# Sche_Main.net
KiCad netlist of a schematic drawn in Altium Designer
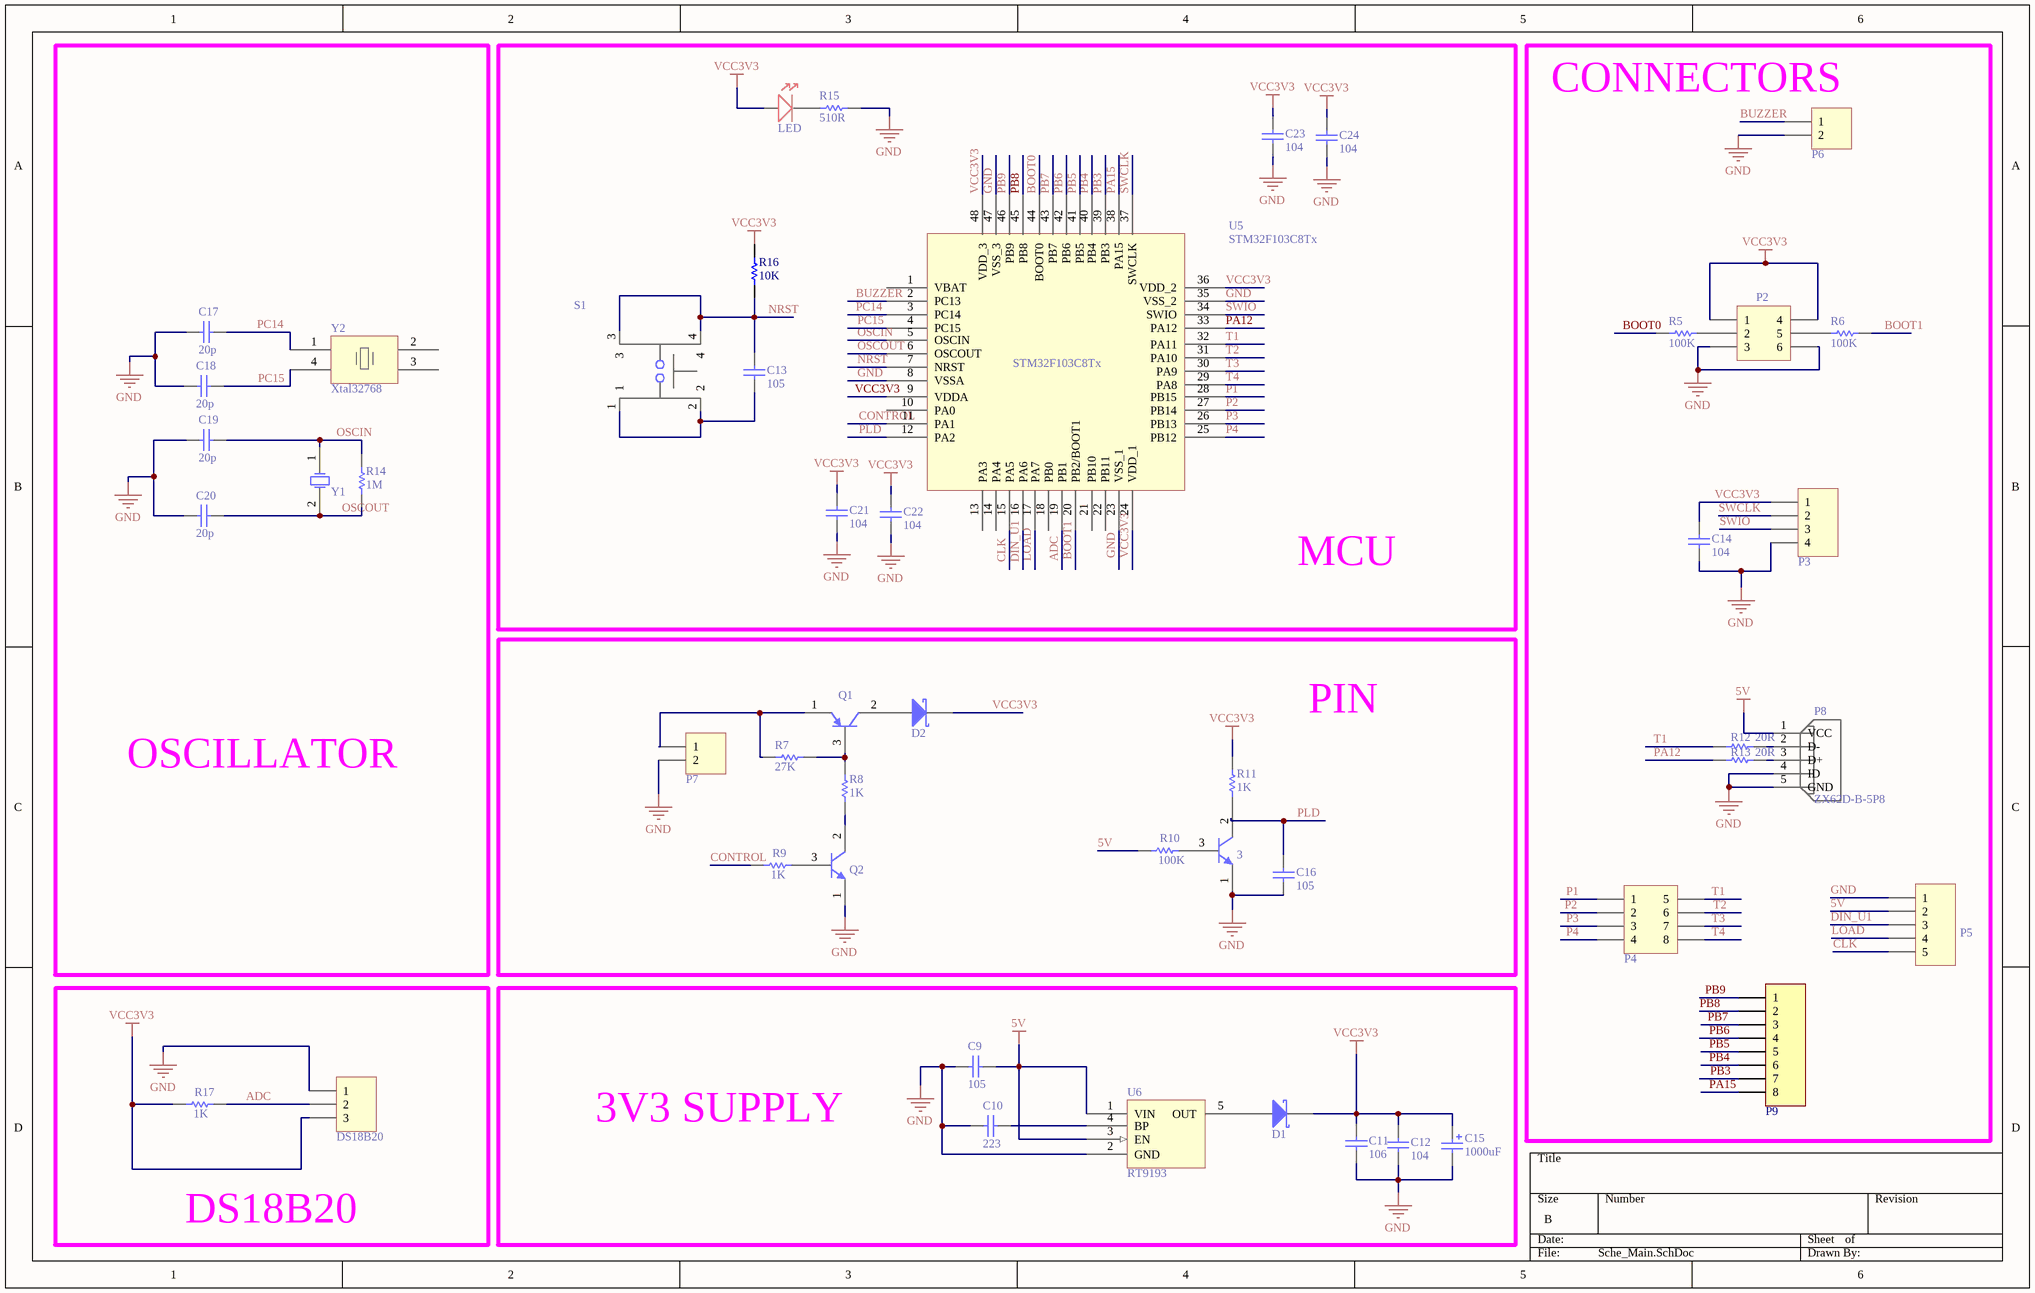
[diagram p0: Sche_Main.SchDoc]

(export (version "E")
  (design (tool "Eeschema 10.0.6"))
  (components
    (comp (ref "3")
      (value "C1815")
      (footprint "SOT23B")
      (description "NPN Bipolar Transistor")
      (libsource (lib "PIF_Library") (part "C1815"))
    )
    (comp (ref "C9")
      (value "105")
      (footprint "CAP-SM-0805")
      (description "Capacitor")
      (fields (field (name "Comment") "Cap Non-Pol SMD"))
      (libsource (lib "PIF_Library") (part "Cap Non-Pol SMD"))
    )
    (comp (ref "C10")
      (value "223")
      (footprint "CAP-SM-0805")
      (description "Capacitor")
      (fields (field (name "Comment") "Cap Non-Pol SMD"))
      (libsource (lib "PIF_Library") (part "Cap Non-Pol SMD"))
    )
    (comp (ref "C11")
      (value "106")
      (footprint "CAP-SM-0805")
      (description "Capacitor")
      (fields (field (name "Comment") "Cap Non-Pol SMD"))
      (libsource (lib "PIF_Library") (part "Cap Non-Pol SMD"))
    )
    (comp (ref "C12")
      (value "104")
      (footprint "CAP-SM-0805")
      (description "Capacitor")
      (fields (field (name "Comment") "Cap Non-Pol SMD"))
      (libsource (lib "PIF_Library") (part "Cap Non-Pol SMD"))
    )
    (comp (ref "C13")
      (value "105")
      (footprint "CAP-SM-0805")
      (description "Capacitor")
      (fields (field (name "Comment") "Cap Non-Pol SMD"))
      (libsource (lib "PIF_Library") (part "Cap Non-Pol SMD"))
    )
    (comp (ref "C14")
      (value "104")
      (footprint "CAP-SM-0805")
      (description "Capacitor")
      (fields (field (name "Comment") "Cap Non-Pol SMD"))
      (libsource (lib "PIF_Library") (part "Cap Non-Pol SMD"))
    )
    (comp (ref "C15")
      (value "1000uF")
      (footprint "CAP ALU SIZE B")
      (description "Polarized Capacitor (Radial)")
      (fields (field (name "Comment") "Cap Pol SMD"))
      (libsource (lib "PIF_Library") (part "Cap Pol SMD"))
    )
    (comp (ref "C16")
      (value "105")
      (footprint "CAP-SM-0805")
      (description "Capacitor")
      (fields (field (name "Comment") "Cap Non-Pol SMD"))
      (libsource (lib "PIF_Library") (part "Cap Non-Pol SMD"))
    )
    (comp (ref "C17")
      (value "20p")
      (footprint "CAP-SM-0805")
      (description "Capacitor")
      (fields (field (name "Comment") "Cap Non-Pol SMD"))
      (libsource (lib "PIF_Library") (part "Cap Non-Pol SMD"))
    )
    (comp (ref "C18")
      (value "20p")
      (footprint "CAP-SM-0805")
      (description "Capacitor")
      (fields (field (name "Comment") "Cap Non-Pol SMD"))
      (libsource (lib "PIF_Library") (part "Cap Non-Pol SMD"))
    )
    (comp (ref "C19")
      (value "20p")
      (footprint "CAP-SM-0805")
      (description "Capacitor")
      (fields (field (name "Comment") "Cap Non-Pol SMD"))
      (libsource (lib "PIF_Library") (part "Cap Non-Pol SMD"))
    )
    (comp (ref "C20")
      (value "20p")
      (footprint "CAP-SM-0805")
      (description "Capacitor")
      (fields (field (name "Comment") "Cap Non-Pol SMD"))
      (libsource (lib "PIF_Library") (part "Cap Non-Pol SMD"))
    )
    (comp (ref "C21")
      (value "104")
      (footprint "CAP-SM-0805")
      (description "Capacitor")
      (fields (field (name "Comment") "Cap Non-Pol SMD"))
      (libsource (lib "PIF_Library") (part "Cap Non-Pol SMD"))
    )
    (comp (ref "C22")
      (value "104")
      (footprint "CAP-SM-0805")
      (description "Capacitor")
      (fields (field (name "Comment") "Cap Non-Pol SMD"))
      (libsource (lib "PIF_Library") (part "Cap Non-Pol SMD"))
    )
    (comp (ref "C23")
      (value "104")
      (footprint "CAP-SM-0805")
      (description "Capacitor")
      (fields (field (name "Comment") "Cap Non-Pol SMD"))
      (libsource (lib "PIF_Library") (part "Cap Non-Pol SMD"))
    )
    (comp (ref "C24")
      (value "104")
      (footprint "CAP-SM-0805")
      (description "Capacitor")
      (fields (field (name "Comment") "Cap Non-Pol SMD"))
      (libsource (lib "PIF_Library") (part "Cap Non-Pol SMD"))
    )
    (comp (ref "D1")
      (value "D Schottky")
      (footprint "SS34")
      (description "Schottky Diode")
      (fields (field (name "PUBLISHER") "Altium Limited"))
      (libsource (lib "PIF_Library") (part "D Schottky"))
    )
    (comp (ref "D2")
      (value "D Schottky")
      (footprint "SS34")
      (description "Schottky Diode")
      (fields (field (name "PUBLISHER") "Altium Limited"))
      (libsource (lib "PIF_Library") (part "D Schottky"))
    )
    (comp (ref "DS18B20")
      (value "Header 3")
      (footprint "QTO-92")
      (description "Header, 3-Pin")
      (fields (field (name "PUBLISHER") "Altium Limited"))
      (libsource (lib "PIF_Library") (part "Header 3"))
    )
    (comp (ref "LED")
      (value "KA-3528EC")
      (footprint "DIOM3228X21N")
      (description "KINGBRIGHT         KA-3528EC             LED, Red, SMD, 2.4mm, 20 mA, 2 V, 627 nm")
      (fields (field (name "MANUFACTURER") "Kingbright"))
      (libsource (lib "WC_Lib") (part "LED_3528"))
    )
    (comp (ref "P2")
      (value "Header 3X2")
      (footprint "JP3x2")
      (description "Header, 3-Pin, Dual row")
      (fields (field (name "PUBLISHER") "Altium Limited"))
      (libsource (lib "PIF_Library") (part "Header 3X2"))
    )
    (comp (ref "P3")
      (value "Header 4")
      (footprint "JP4")
      (description "Header, 4-Pin")
      (fields (field (name "PUBLISHER") "Altium Limited"))
      (libsource (lib "PIF_Library") (part "Header 4"))
    )
    (comp (ref "P4")
      (value "Header 4X2")
      (footprint "JP4x2")
      (description "Header, 4-Pin, Dual row")
      (fields (field (name "PUBLISHER") "Altium Limited"))
      (libsource (lib "PIF_Library") (part "Header 4X2"))
    )
    (comp (ref "P5")
      (value "Header 5")
      (footprint "JP5")
      (description "Header, 5-Pin")
      (fields (field (name "PUBLISHER") "Altium Limited"))
      (libsource (lib "PIF_Library") (part "Header 5"))
    )
    (comp (ref "P6")
      (value "Domino 2")
      (footprint "DOMINO 2- 5mm")
      (description "Domino, 2-Pin")
      (fields (field (name "PUBLISHER") "Altium Limited"))
      (libsource (lib "PIF_Library") (part "Domino 2"))
    )
    (comp (ref "P7")
      (value "Header 2")
      (footprint "JP2")
      (description "Header, 2-Pin")
      (fields (field (name "PUBLISHER") "Altium Limited"))
      (libsource (lib "PIF_Library") (part "Header 2"))
    )
    (comp (ref "P8")
      (value "ZX62D-B-5P8")
      (footprint "HRS_ZX62D-B-5P8")
      (description "SMD+DIP Micro USB; MICRO-B-SMD")
      (fields (field (name "MF") "Hirose"))
      (libsource (lib "ZX62D-B-5P8") (part "ZX62D-B-5P8"))
    )
    (comp (ref "P9")
      (value "Header 8")
      (footprint "JP8")
      (description "Header, 8-Pin")
      (fields (field (name "PUBLISHER") "Altium Limited"))
      (libsource (lib "PIF_Library") (part "Header 8"))
    )
    (comp (ref "Q1")
      (value "A1015")
      (footprint "SOT23B")
      (description "PNP Bipolar Transistor")
      (libsource (lib "PIF_Library") (part "A1015"))
    )
    (comp (ref "Q2")
      (value "C1815")
      (footprint "SOT23B")
      (description "NPN Bipolar Transistor")
      (libsource (lib "PIF_Library") (part "C1815"))
    )
    (comp (ref "R5")
      (value "100K")
      (footprint "RES-SM-0805")
      (description "Resistor")
      (fields (field (name "Comment") "RESISTOR SMD"))
      (libsource (lib "PIF_Library") (part "RESISTOR SMD"))
    )
    (comp (ref "R6")
      (value "100K")
      (footprint "RES-SM-0805")
      (description "Resistor")
      (fields (field (name "Comment") "RESISTOR SMD"))
      (libsource (lib "PIF_Library") (part "RESISTOR SMD"))
    )
    (comp (ref "R7")
      (value "27K")
      (footprint "RES-SM-0805")
      (description "Resistor")
      (fields (field (name "Comment") "RESISTOR SMD"))
      (libsource (lib "PIF_Library") (part "RESISTOR SMD"))
    )
    (comp (ref "R8")
      (value "1K")
      (footprint "RES-SM-0805")
      (description "Resistor")
      (fields (field (name "Comment") "RESISTOR SMD"))
      (libsource (lib "PIF_Library") (part "RESISTOR SMD"))
    )
    (comp (ref "R9")
      (value "1K")
      (footprint "RES-SM-0805")
      (description "Resistor")
      (fields (field (name "Comment") "RESISTOR SMD"))
      (libsource (lib "PIF_Library") (part "RESISTOR SMD"))
    )
    (comp (ref "R10")
      (value "100K")
      (footprint "RES-SM-0805")
      (description "Resistor")
      (fields (field (name "Comment") "RESISTOR SMD"))
      (libsource (lib "PIF_Library") (part "RESISTOR SMD"))
    )
    (comp (ref "R11")
      (value "1K")
      (footprint "RES-SM-0805")
      (description "Resistor")
      (fields (field (name "Comment") "RESISTOR SMD"))
      (libsource (lib "PIF_Library") (part "RESISTOR SMD"))
    )
    (comp (ref "R12")
      (value "20R")
      (footprint "RES-SM-0805")
      (description "Resistor")
      (fields (field (name "Comment") "RESISTOR SMD"))
      (libsource (lib "PIF_Library") (part "RESISTOR SMD"))
    )
    (comp (ref "R13")
      (value "20R")
      (footprint "RES-SM-0805")
      (description "Resistor")
      (fields (field (name "Comment") "RESISTOR SMD"))
      (libsource (lib "PIF_Library") (part "RESISTOR SMD"))
    )
    (comp (ref "R14")
      (value "1M")
      (footprint "RES-SM-0805")
      (description "Resistor")
      (fields (field (name "Comment") "RESISTOR SMD"))
      (libsource (lib "PIF_Library") (part "RESISTOR SMD"))
    )
    (comp (ref "R15")
      (value "510R")
      (footprint "RES-SM-0805")
      (description "Resistor")
      (fields (field (name "Comment") "RESISTOR SMD"))
      (libsource (lib "PIF_Library") (part "RESISTOR SMD"))
    )
    (comp (ref "R16")
      (value "10K")
      (footprint "RES-SM-0805")
      (description "Resistor")
      (fields (field (name "Comment") "RESISTOR SMD"))
      (libsource (lib "PIF_Library") (part "RESISTOR SMD"))
    )
    (comp (ref "R17")
      (value "1K")
      (footprint "RES-SM-0805")
      (description "Resistor")
      (fields (field (name "Comment") "RESISTOR SMD"))
      (libsource (lib "PIF_Library") (part "RESISTOR SMD"))
    )
    (comp (ref "S1")
      (value "TL3342F160QG")
      (footprint "SW_TL3342F160QG")
      (description "TL3342 Series SPST 1.6 N Round Button Gull Wing Surface Mount Tactile Switch")
      (fields (field (name "MF") "E-Switch"))
      (libsource (lib "TL3342F160QG") (part "TL3342F160QG"))
    )
    (comp (ref "U5")
      (value "STM32F103C8Tx")
      (footprint "TSQFP50P900X900X160-48N")
      (description "MCU 32-bit STM32F ARM Cortex M3 RISC 64KB Flash 2.5V/3.3V 48-Pin LQFP Tray")
      (fields
        (field (name "MANUFACTURER") "STMicroelectronics")
        (field (name "MANUFACTURER PART NUMBER") "STM32F103C8T6")
      )
      (libsource (lib "WC_Lib") (part "STM32F103C8Tx"))
    )
    (comp (ref "U6")
      (value "RT9193")
      (footprint "SOT95P279X129-5N")
      (description "RICHTEK         RT9193-15GB            IC, LDO, FIXED, 1.5V, 0.3A, SOT-23-5")
      (fields (field (name "MANUFACTURER") "Richtek") (field (name "MANUFACTURER PART NUMBER") "RT9193-15GB"))
      (libsource (lib "WC_Lib") (part "RT9193"))
    )
    (comp (ref "Y1")
      (value "XTAL")
      (footprint "XT2")
      (description "Crystal Oscillator")
      (fields (field (name "PUBLISHER") "Altium Limited"))
      (libsource (lib "PIF_Library") (part "XTAL"))
    )
    (comp (ref "Y2") (value "Xtal32768") (libsource (lib "WC_Lib") (part "Xtal32768")))
  )
  (nets
    (net (code "1") (name "/ADC") (class "Default")
      (node (ref "DS18B20") (pin "2") (pinfunction "2_2") (pintype "passive"))
      (node (ref "R17") (pin "2") (pinfunction "2_2") (pintype "passive"))
      (node (ref "U5") (pin "19") (pinfunction "PB1_19") (pintype "passive"))
    )
    (net (code "2") (name "/BOOT0") (class "Default")
      (node (ref "R5") (pin "1") (pinfunction "1_1") (pintype "passive"))
      (node (ref "U5") (pin "44") (pinfunction "BOOT0_44") (pintype "passive"))
    )
    (net (code "3") (name "/BOOT1") (class "Default")
      (node (ref "R6") (pin "2") (pinfunction "2_2") (pintype "passive"))
      (node (ref "U5") (pin "20") (pinfunction "PB2/BOOT1_20") (pintype "passive"))
    )
    (net (code "4") (name "/BUZZER") (class "Default")
      (node (ref "P6") (pin "1") (pinfunction "1_1") (pintype "passive"))
      (node (ref "U5") (pin "2") (pinfunction "PC13_2") (pintype "passive"))
    )
    (net (code "5") (name "/CLK") (class "Default")
      (node (ref "P5") (pin "5") (pinfunction "5_5") (pintype "passive"))
      (node (ref "U5") (pin "15") (pinfunction "PA5_15") (pintype "passive"))
    )
    (net (code "6") (name "/CONTROL") (class "Default")
      (node (ref "R9") (pin "1") (pinfunction "1_1") (pintype "passive"))
      (node (ref "U5") (pin "11") (pinfunction "PA1_11") (pintype "passive"))
    )
    (net (code "7") (name "/DIN_U1") (class "Default")
      (node (ref "P5") (pin "3") (pinfunction "3_3") (pintype "passive"))
      (node (ref "U5") (pin "16") (pinfunction "PA6_16") (pintype "passive"))
    )
    (net (code "8") (name "/LOAD") (class "Default")
      (node (ref "P5") (pin "4") (pinfunction "4_4") (pintype "passive"))
      (node (ref "U5") (pin "17") (pinfunction "PA7_17") (pintype "passive"))
    )
    (net (code "9") (name "/NRST") (class "Default")
      (node (ref "C13") (pin "2") (pinfunction "2_2") (pintype "passive"))
      (node (ref "R16") (pin "1") (pinfunction "1_1") (pintype "passive"))
      (node (ref "S1") (pin "3") (pinfunction "3_3") (pintype "passive"))
      (node (ref "S1") (pin "4") (pinfunction "4_4") (pintype "passive"))
      (node (ref "U5") (pin "7") (pinfunction "NRST_7") (pintype "passive"))
    )
    (net (code "10") (name "/OSCIN") (class "Default")
      (node (ref "C19") (pin "2") (pinfunction "2_2") (pintype "passive"))
      (node (ref "R14") (pin "2") (pinfunction "2_2") (pintype "passive"))
      (node (ref "U5") (pin "5") (pinfunction "OSCIN_5") (pintype "passive"))
      (node (ref "Y1") (pin "1") (pinfunction "OSC1_1") (pintype "passive"))
    )
    (net (code "11") (name "/OSCOUT") (class "Default")
      (node (ref "C20") (pin "2") (pinfunction "2_2") (pintype "passive"))
      (node (ref "R14") (pin "1") (pinfunction "1_1") (pintype "passive"))
      (node (ref "U5") (pin "6") (pinfunction "OSCOUT_6") (pintype "passive"))
      (node (ref "Y1") (pin "2") (pinfunction "OSC2_2") (pintype "passive"))
    )
    (net (code "12") (name "/P1") (class "Default")
      (node (ref "P4") (pin "1") (pinfunction "1_1") (pintype "passive"))
      (node (ref "U5") (pin "28") (pinfunction "PB15_28") (pintype "passive"))
    )
    (net (code "13") (name "/P2") (class "Default")
      (node (ref "P4") (pin "2") (pinfunction "2_2") (pintype "passive"))
      (node (ref "U5") (pin "27") (pinfunction "PB14_27") (pintype "passive"))
    )
    (net (code "14") (name "/P3") (class "Default")
      (node (ref "P4") (pin "3") (pinfunction "3_3") (pintype "passive"))
      (node (ref "U5") (pin "26") (pinfunction "PB13_26") (pintype "passive"))
    )
    (net (code "15") (name "/P4") (class "Default")
      (node (ref "P4") (pin "4") (pinfunction "4_4") (pintype "passive"))
      (node (ref "U5") (pin "25") (pinfunction "PB12_25") (pintype "passive"))
    )
    (net (code "16") (name "/PA12") (class "Default")
      (node (ref "R13") (pin "1") (pinfunction "1_1") (pintype "passive"))
      (node (ref "U5") (pin "33") (pinfunction "PA12_33") (pintype "passive"))
    )
    (net (code "17") (name "/PA15") (class "Default")
      (node (ref "P9") (pin "8") (pinfunction "8_8") (pintype "passive"))
      (node (ref "U5") (pin "38") (pinfunction "PA15_38") (pintype "passive"))
    )
    (net (code "18") (name "/PB3") (class "Default")
      (node (ref "P9") (pin "7") (pinfunction "7_7") (pintype "passive"))
      (node (ref "U5") (pin "39") (pinfunction "PB3_39") (pintype "passive"))
    )
    (net (code "19") (name "/PB4") (class "Default")
      (node (ref "P9") (pin "6") (pinfunction "6_6") (pintype "passive"))
      (node (ref "U5") (pin "40") (pinfunction "PB4_40") (pintype "passive"))
    )
    (net (code "20") (name "/PB5") (class "Default")
      (node (ref "P9") (pin "5") (pinfunction "5_5") (pintype "passive"))
      (node (ref "U5") (pin "41") (pinfunction "PB5_41") (pintype "passive"))
    )
    (net (code "21") (name "/PB6") (class "Default")
      (node (ref "P9") (pin "4") (pinfunction "4_4") (pintype "passive"))
      (node (ref "U5") (pin "42") (pinfunction "PB6_42") (pintype "passive"))
    )
    (net (code "22") (name "/PB7") (class "Default")
      (node (ref "P9") (pin "3") (pinfunction "3_3") (pintype "passive"))
      (node (ref "U5") (pin "43") (pinfunction "PB7_43") (pintype "passive"))
    )
    (net (code "23") (name "/PB8") (class "Default")
      (node (ref "P9") (pin "2") (pinfunction "2_2") (pintype "passive"))
      (node (ref "U5") (pin "45") (pinfunction "PB8_45") (pintype "passive"))
    )
    (net (code "24") (name "/PB9") (class "Default")
      (node (ref "P9") (pin "1") (pinfunction "1_1") (pintype "passive"))
      (node (ref "U5") (pin "46") (pinfunction "PB9_46") (pintype "passive"))
    )
    (net (code "25") (name "/PC14") (class "Default")
      (node (ref "C17") (pin "2") (pinfunction "2_2") (pintype "passive"))
      (node (ref "U5") (pin "3") (pinfunction "PC14_3") (pintype "passive"))
      (node (ref "Y2") (pin "1") (pinfunction "1_1") (pintype "passive"))
    )
    (net (code "26") (name "/PC15") (class "Default")
      (node (ref "C18") (pin "2") (pinfunction "2_2") (pintype "passive"))
      (node (ref "U5") (pin "4") (pinfunction "PC15_4") (pintype "passive"))
      (node (ref "Y2") (pin "4") (pinfunction "4_4") (pintype "passive"))
    )
    (net (code "27") (name "/PLD") (class "Default")
      (node (ref "C16") (pin "2") (pinfunction "2_2") (pintype "passive"))
      (node (ref "U5") (pin "12") (pinfunction "PA2_12") (pintype "passive"))
    )
    (net (code "28") (name "/SWCLK") (class "Default")
      (node (ref "P3") (pin "2") (pinfunction "2_2") (pintype "passive"))
      (node (ref "U5") (pin "37") (pinfunction "SWCLK_37") (pintype "passive"))
    )
    (net (code "29") (name "/SWIO") (class "Default")
      (node (ref "P3") (pin "3") (pinfunction "3_3") (pintype "passive"))
      (node (ref "U5") (pin "34") (pinfunction "SWIO_34") (pintype "passive"))
    )
    (net (code "30") (name "/T1") (class "Default")
      (node (ref "P4") (pin "5") (pinfunction "5_5") (pintype "passive"))
      (node (ref "R12") (pin "1") (pinfunction "1_1") (pintype "passive"))
      (node (ref "U5") (pin "32") (pinfunction "PA11_32") (pintype "passive"))
    )
    (net (code "31") (name "/T2") (class "Default")
      (node (ref "P4") (pin "6") (pinfunction "6_6") (pintype "passive"))
      (node (ref "U5") (pin "31") (pinfunction "PA10_31") (pintype "passive"))
    )
    (net (code "32") (name "/T3") (class "Default")
      (node (ref "P4") (pin "7") (pinfunction "7_7") (pintype "passive"))
      (node (ref "U5") (pin "30") (pinfunction "PA9_30") (pintype "passive"))
    )
    (net (code "33") (name "/T4") (class "Default")
      (node (ref "P4") (pin "8") (pinfunction "8_8") (pintype "passive"))
      (node (ref "U5") (pin "29") (pinfunction "PA8_29") (pintype "passive"))
    )
    (net (code "34") (name "5V") (class "Default")
      (node (ref "C9") (pin "2") (pinfunction "2_2") (pintype "passive"))
      (node (ref "P5") (pin "2") (pinfunction "2_2") (pintype "passive"))
      (node (ref "P8") (pin "1") (pinfunction "VCC_1") (pintype "power_in"))
      (node (ref "R10") (pin "1") (pinfunction "1_1") (pintype "passive"))
      (node (ref "U6") (pin "1") (pinfunction "VIN_1") (pintype "power_in"))
      (node (ref "U6") (pin "3") (pinfunction "EN_3") (pintype "input"))
    )
    (net (code "35") (name "GND") (class "Default")
      (node (ref "3") (pin "1") (pinfunction "E_1") (pintype "passive"))
      (node (ref "C10") (pin "1") (pinfunction "1_1") (pintype "passive"))
      (node (ref "C11") (pin "1") (pinfunction "1_1") (pintype "passive"))
      (node (ref "C12") (pin "1") (pinfunction "1_1") (pintype "passive"))
      (node (ref "C14") (pin "1") (pinfunction "1_1") (pintype "passive"))
      (node (ref "C15") (pin "2") (pinfunction "2_2") (pintype "passive"))
      (node (ref "C16") (pin "1") (pinfunction "1_1") (pintype "passive"))
      (node (ref "C17") (pin "1") (pinfunction "1_1") (pintype "passive"))
      (node (ref "C18") (pin "1") (pinfunction "1_1") (pintype "passive"))
      (node (ref "C19") (pin "1") (pinfunction "1_1") (pintype "passive"))
      (node (ref "C20") (pin "1") (pinfunction "1_1") (pintype "passive"))
      (node (ref "C21") (pin "1") (pinfunction "1_1") (pintype "passive"))
      (node (ref "C22") (pin "1") (pinfunction "1_1") (pintype "passive"))
      (node (ref "C23") (pin "1") (pinfunction "1_1") (pintype "passive"))
      (node (ref "C24") (pin "1") (pinfunction "1_1") (pintype "passive"))
      (node (ref "C9") (pin "1") (pinfunction "1_1") (pintype "passive"))
      (node (ref "DS18B20") (pin "1") (pinfunction "1_1") (pintype "passive"))
      (node (ref "P2") (pin "3") (pinfunction "3_3") (pintype "passive"))
      (node (ref "P2") (pin "6") (pinfunction "6_6") (pintype "passive"))
      (node (ref "P3") (pin "4") (pinfunction "4_4") (pintype "passive"))
      (node (ref "P5") (pin "1") (pinfunction "1_1") (pintype "passive"))
      (node (ref "P6") (pin "2") (pinfunction "2_2") (pintype "passive"))
      (node (ref "P7") (pin "2") (pinfunction "2_2") (pintype "passive"))
      (node (ref "P8") (pin "4") (pinfunction "ID_4") (pintype "passive"))
      (node (ref "P8") (pin "5") (pinfunction "GND_5") (pintype "power_in"))
      (node (ref "Q2") (pin "1") (pinfunction "E_1") (pintype "passive"))
      (node (ref "R15") (pin "2") (pinfunction "2_2") (pintype "passive"))
      (node (ref "U5") (pin "23") (pinfunction "VSS_1_23") (pintype "passive"))
      (node (ref "U5") (pin "35") (pinfunction "VSS_2_35") (pintype "passive"))
      (node (ref "U5") (pin "47") (pinfunction "VSS_3_47") (pintype "passive"))
      (node (ref "U5") (pin "8") (pinfunction "VSSA_8") (pintype "passive"))
      (node (ref "U6") (pin "2") (pinfunction "GND_2") (pintype "power_in"))
    )
    (net (code "36") (name "Net-(3-B)") (class "Default")
      (node (ref "3") (pin "3") (pinfunction "B_3") (pintype "passive"))
      (node (ref "R10") (pin "2") (pinfunction "2_2") (pintype "passive"))
    )
    (net (code "37") (name "Net-(3-C)") (class "Default")
      (node (ref "3") (pin "2") (pinfunction "C_2") (pintype "passive"))
      (node (ref "R11") (pin "1") (pinfunction "1_1") (pintype "passive"))
    )
    (net (code "38") (name "Net-(C13-Pad1)") (class "Default")
      (node (ref "C13") (pin "1") (pinfunction "1_1") (pintype "passive"))
      (node (ref "S1") (pin "1") (pinfunction "1_1") (pintype "passive"))
      (node (ref "S1") (pin "2") (pinfunction "2_2") (pintype "passive"))
    )
    (net (code "39") (name "Net-(D1-A)") (class "Default")
      (node (ref "D1") (pin "1") (pinfunction "A_1") (pintype "passive"))
      (node (ref "U6") (pin "5") (pinfunction "OUT_5") (pintype "passive"))
    )
    (net (code "40") (name "Net-(D2-A)") (class "Default")
      (node (ref "D2") (pin "1") (pinfunction "A_1") (pintype "passive"))
      (node (ref "Q1") (pin "2") (pinfunction "C_2") (pintype "passive"))
    )
    (net (code "41") (name "Net-(LED-Pad2)") (class "Default")
      (node (ref "LED") (pin "2") (pinfunction "2_2") (pintype "passive"))
      (node (ref "R15") (pin "1") (pinfunction "1_1") (pintype "passive"))
    )
    (net (code "42") (name "Net-(P2-Pad2)") (class "Default")
      (node (ref "P2") (pin "2") (pinfunction "2_2") (pintype "passive"))
      (node (ref "R5") (pin "2") (pinfunction "2_2") (pintype "passive"))
    )
    (net (code "43") (name "Net-(P2-Pad5)") (class "Default")
      (node (ref "P2") (pin "5") (pinfunction "5_5") (pintype "passive"))
      (node (ref "R6") (pin "1") (pinfunction "1_1") (pintype "passive"))
    )
    (net (code "44") (name "Net-(P8-D+)") (class "Default")
      (node (ref "P8") (pin "3") (pinfunction "D+_3") (pintype "passive"))
      (node (ref "R13") (pin "2") (pinfunction "2_2") (pintype "passive"))
    )
    (net (code "45") (name "Net-(P8-D-)") (class "Default")
      (node (ref "P8") (pin "2") (pinfunction "D-_2") (pintype "passive"))
      (node (ref "R12") (pin "2") (pinfunction "2_2") (pintype "passive"))
    )
    (net (code "46") (name "Net-(Q1-B)") (class "Default")
      (node (ref "Q1") (pin "3") (pinfunction "B_3") (pintype "passive"))
      (node (ref "R7") (pin "2") (pinfunction "2_2") (pintype "passive"))
      (node (ref "R8") (pin "2") (pinfunction "2_2") (pintype "passive"))
    )
    (net (code "47") (name "Net-(Q1-E)") (class "Default")
      (node (ref "P7") (pin "1") (pinfunction "1_1") (pintype "passive"))
      (node (ref "Q1") (pin "1") (pinfunction "E_1") (pintype "passive"))
      (node (ref "R7") (pin "1") (pinfunction "1_1") (pintype "passive"))
    )
    (net (code "48") (name "Net-(Q2-B)") (class "Default")
      (node (ref "Q2") (pin "3") (pinfunction "B_3") (pintype "passive"))
      (node (ref "R9") (pin "2") (pinfunction "2_2") (pintype "passive"))
    )
    (net (code "49") (name "Net-(Q2-C)") (class "Default")
      (node (ref "Q2") (pin "2") (pinfunction "C_2") (pintype "passive"))
      (node (ref "R8") (pin "1") (pinfunction "1_1") (pintype "passive"))
    )
    (net (code "50") (name "Net-(U6-BP)") (class "Default")
      (node (ref "C10") (pin "2") (pinfunction "2_2") (pintype "passive"))
      (node (ref "U6") (pin "4") (pinfunction "BP_4") (pintype "passive"))
    )
    (net (code "51") (name "VCC3V3") (class "Default")
      (node (ref "C11") (pin "2") (pinfunction "2_2") (pintype "passive"))
      (node (ref "C12") (pin "2") (pinfunction "2_2") (pintype "passive"))
      (node (ref "C14") (pin "2") (pinfunction "2_2") (pintype "passive"))
      (node (ref "C15") (pin "1") (pinfunction "1_1") (pintype "passive"))
      (node (ref "C21") (pin "2") (pinfunction "2_2") (pintype "passive"))
      (node (ref "C22") (pin "2") (pinfunction "2_2") (pintype "passive"))
      (node (ref "C23") (pin "2") (pinfunction "2_2") (pintype "passive"))
      (node (ref "C24") (pin "2") (pinfunction "2_2") (pintype "passive"))
      (node (ref "D1") (pin "2") (pinfunction "K_2") (pintype "passive"))
      (node (ref "D2") (pin "2") (pinfunction "K_2") (pintype "passive"))
      (node (ref "DS18B20") (pin "3") (pinfunction "3_3") (pintype "passive"))
      (node (ref "LED") (pin "1") (pinfunction "1_1") (pintype "passive"))
      (node (ref "P2") (pin "1") (pinfunction "1_1") (pintype "passive"))
      (node (ref "P2") (pin "4") (pinfunction "4_4") (pintype "passive"))
      (node (ref "P3") (pin "1") (pinfunction "1_1") (pintype "passive"))
      (node (ref "R11") (pin "2") (pinfunction "2_2") (pintype "passive"))
      (node (ref "R16") (pin "2") (pinfunction "2_2") (pintype "passive"))
      (node (ref "R17") (pin "1") (pinfunction "1_1") (pintype "passive"))
      (node (ref "U5") (pin "24") (pinfunction "VDD_1_24") (pintype "passive"))
      (node (ref "U5") (pin "36") (pinfunction "VDD_2_36") (pintype "passive"))
      (node (ref "U5") (pin "48") (pinfunction "VDD_3_48") (pintype "passive"))
      (node (ref "U5") (pin "9") (pinfunction "VDDA_9") (pintype "passive"))
    )
    (net (code "52") (name "unconnected-(U5-PA0-Pad10)") (class "Default")
      (node (ref "U5") (pin "10") (pinfunction "PA0_10") (pintype "passive"))
    )
    (net (code "53") (name "unconnected-(U5-PA3-Pad13)") (class "Default")
      (node (ref "U5") (pin "13") (pinfunction "PA3_13") (pintype "passive"))
    )
    (net (code "54") (name "unconnected-(U5-PA4-Pad14)") (class "Default")
      (node (ref "U5") (pin "14") (pinfunction "PA4_14") (pintype "passive"))
    )
    (net (code "55") (name "unconnected-(U5-PB0-Pad18)") (class "Default")
      (node (ref "U5") (pin "18") (pinfunction "PB0_18") (pintype "passive"))
    )
    (net (code "56") (name "unconnected-(U5-PB10-Pad21)") (class "Default")
      (node (ref "U5") (pin "21") (pinfunction "PB10_21") (pintype "passive"))
    )
    (net (code "57") (name "unconnected-(U5-PB11-Pad22)") (class "Default")
      (node (ref "U5") (pin "22") (pinfunction "PB11_22") (pintype "passive"))
    )
    (net (code "58") (name "unconnected-(U5-VBAT-Pad1)") (class "Default")
      (node (ref "U5") (pin "1") (pinfunction "VBAT_1") (pintype "passive"))
    )
    (net (code "59") (name "unconnected-(Y2-Pad2)") (class "Default")
      (node (ref "Y2") (pin "2") (pinfunction "2_2") (pintype "passive"))
    )
    (net (code "60") (name "unconnected-(Y2-Pad3)") (class "Default")
      (node (ref "Y2") (pin "3") (pinfunction "3_3") (pintype "passive"))
    )
  )
)
